# sensorboard_14.net
KiCad netlist of a schematic drawn in EAGLE
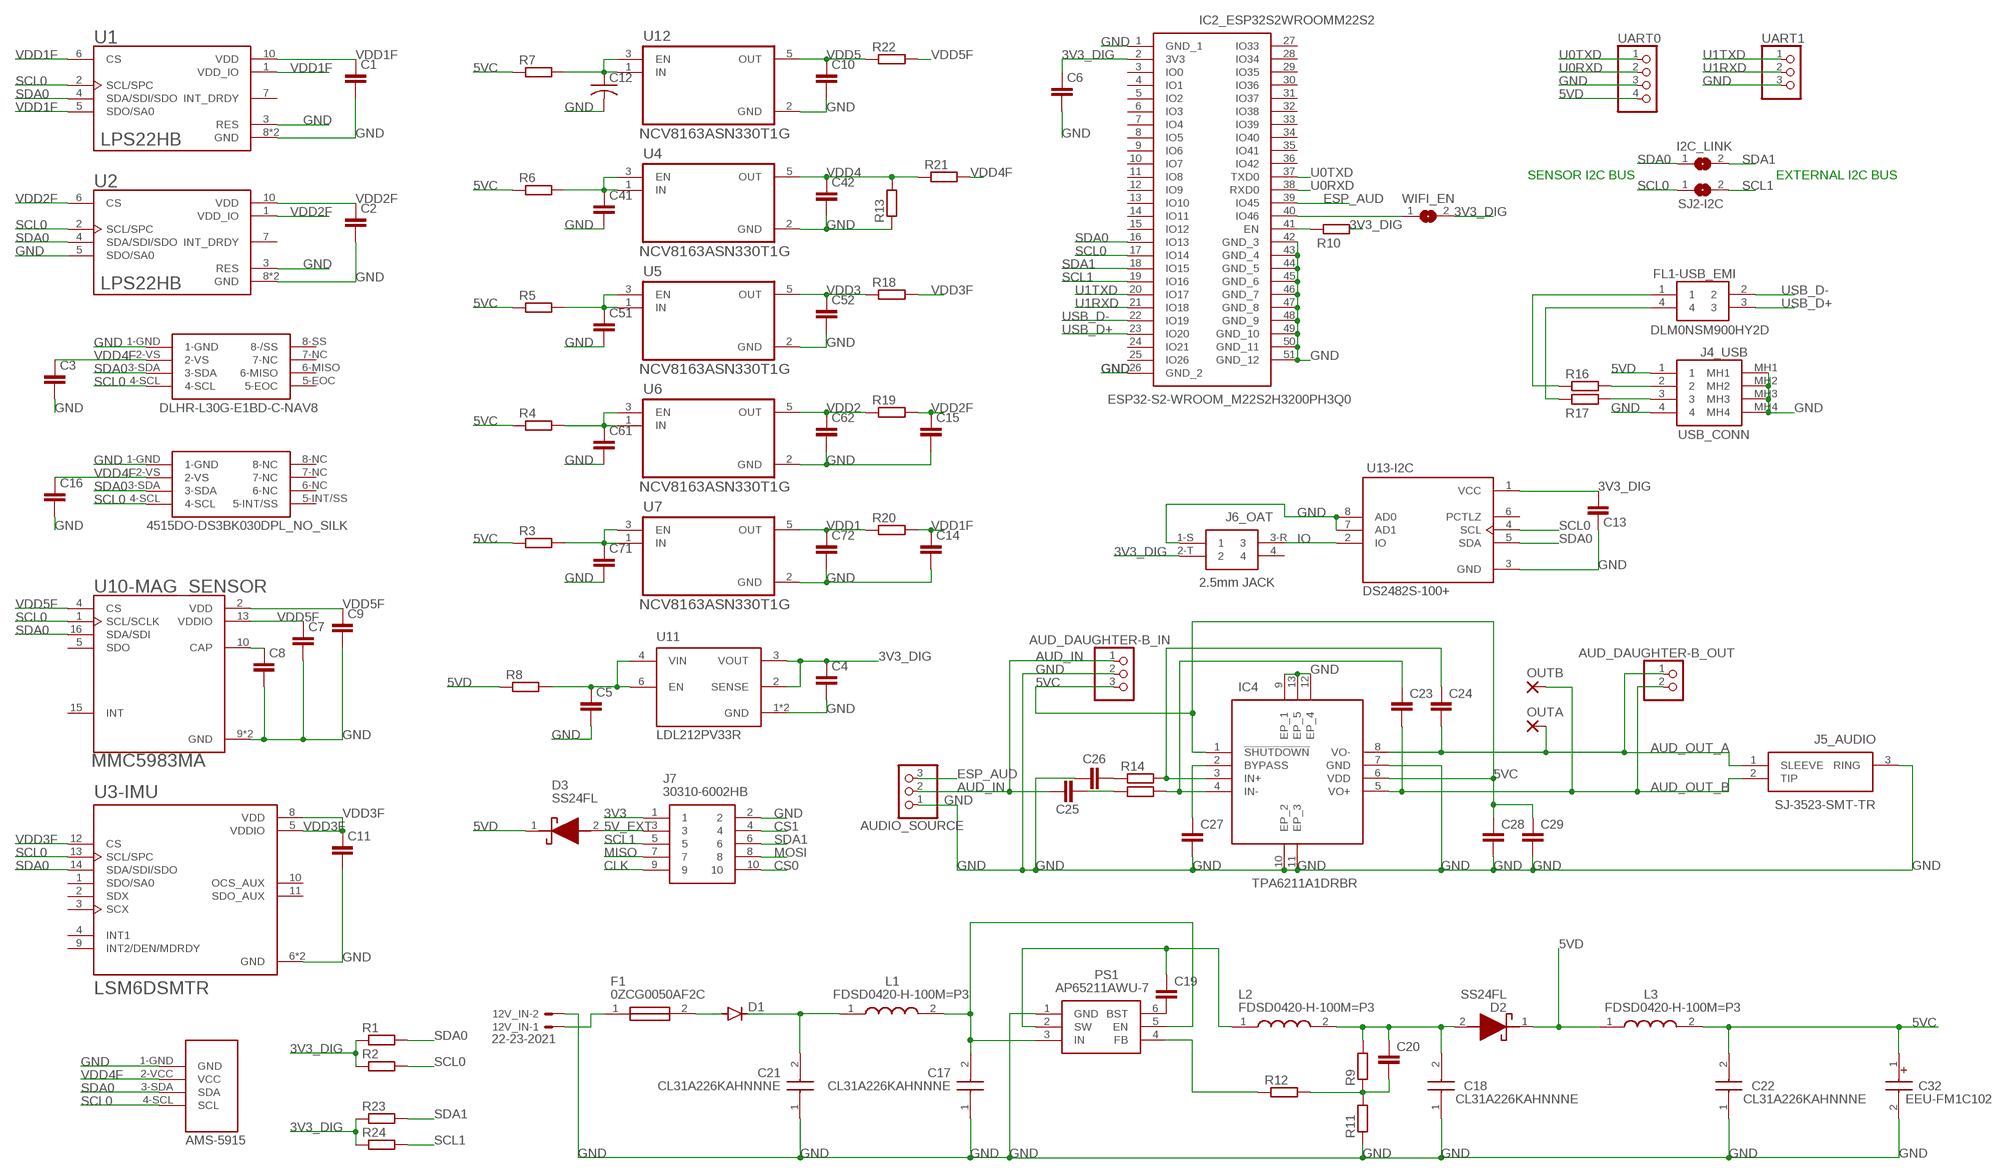
[diagram p0: schematic, sheet 1]

(export (version "E")
  (design (tool "Eeschema 10.0.6"))
  (components
    (comp (ref "12V_IN")
      (value "22-23-2021")
      (footprint "eagle-import:22-23-2021")
      (fields (field (name "MF") "MOLEX"))
      (libsource (lib "eagle-import") (part "22-23-2021"))
    )
    (comp (ref "AUDIO_SOURCE")
      (value "PINHD-1X3")
      (footprint "eagle-import:1X03")
      (libsource (lib "eagle-import") (part "PINHD-1X3"))
    )
    (comp (ref "AUD_DAUGHTER-B_IN")
      (value "PINHD-1X3")
      (footprint "eagle-import:1X03")
      (libsource (lib "eagle-import") (part "PINHD-1X3"))
    )
    (comp (ref "AUD_DAUGHTER-B_OUT")
      (value "PINHD-1X2")
      (footprint "eagle-import:1X02")
      (libsource (lib "eagle-import") (part "PINHD-1X2"))
    )
    (comp (ref "C1")
      (value "C-EUC0603")
      (footprint "eagle-import:C0603")
      (libsource (lib "eagle-import") (part "C-EUC0603"))
    )
    (comp (ref "C2")
      (value "C-EUC0603")
      (footprint "eagle-import:C0603")
      (libsource (lib "eagle-import") (part "C-EUC0603"))
    )
    (comp (ref "C3")
      (value "C-EUC0805")
      (footprint "eagle-import:C0805")
      (libsource (lib "eagle-import") (part "C-EUC0805"))
    )
    (comp (ref "C4")
      (value "C-EUC0805")
      (footprint "eagle-import:C0805")
      (libsource (lib "eagle-import") (part "C-EUC0805"))
    )
    (comp (ref "C5")
      (value "C-EUC0805")
      (footprint "eagle-import:C0805")
      (libsource (lib "eagle-import") (part "C-EUC0805"))
    )
    (comp (ref "C6")
      (value "C-EUC0805")
      (footprint "eagle-import:C0805")
      (libsource (lib "eagle-import") (part "C-EUC0805"))
    )
    (comp (ref "C7")
      (value "C-EUC0805")
      (footprint "eagle-import:C0805")
      (libsource (lib "eagle-import") (part "C-EUC0805"))
    )
    (comp (ref "C8")
      (value "C-EUC0805")
      (footprint "eagle-import:C0805")
      (libsource (lib "eagle-import") (part "C-EUC0805"))
    )
    (comp (ref "C9")
      (value "C-EUC0805")
      (footprint "eagle-import:C0805")
      (libsource (lib "eagle-import") (part "C-EUC0805"))
    )
    (comp (ref "C10")
      (value "C-EUC0805")
      (footprint "eagle-import:C0805")
      (libsource (lib "eagle-import") (part "C-EUC0805"))
    )
    (comp (ref "C11")
      (value "C-EUC0805")
      (footprint "eagle-import:C0805")
      (libsource (lib "eagle-import") (part "C-EUC0805"))
    )
    (comp (ref "C12")
      (value "C-USC0805")
      (footprint "eagle-import:C0805")
      (libsource (lib "eagle-import") (part "C-USC0805"))
    )
    (comp (ref "C13")
      (value "C-EUC0805")
      (footprint "eagle-import:C0805")
      (libsource (lib "eagle-import") (part "C-EUC0805"))
    )
    (comp (ref "C14")
      (value "C-EUC0805")
      (footprint "eagle-import:C0805")
      (libsource (lib "eagle-import") (part "C-EUC0805"))
    )
    (comp (ref "C15")
      (value "C-EUC0805")
      (footprint "eagle-import:C0805")
      (libsource (lib "eagle-import") (part "C-EUC0805"))
    )
    (comp (ref "C16")
      (value "C-EUC0805")
      (footprint "eagle-import:C0805")
      (libsource (lib "eagle-import") (part "C-EUC0805"))
    )
    (comp (ref "C17")
      (value "CL31A226KAHNNNE")
      (footprint "eagle-import:CAPC3216X180N")
      (libsource (lib "eagle-import") (part "CL31A226KAHNNNE"))
    )
    (comp (ref "C18")
      (value "CL31A226KAHNNNE")
      (footprint "eagle-import:CAPC3216X180N")
      (libsource (lib "eagle-import") (part "CL31A226KAHNNNE"))
    )
    (comp (ref "C19")
      (value "C-EUC0805")
      (footprint "eagle-import:C0805")
      (libsource (lib "eagle-import") (part "C-EUC0805"))
    )
    (comp (ref "C20")
      (value "C-EUC0805")
      (footprint "eagle-import:C0805")
      (libsource (lib "eagle-import") (part "C-EUC0805"))
    )
    (comp (ref "C21")
      (value "CL31A226KAHNNNE")
      (footprint "eagle-import:CAPC3216X180N")
      (libsource (lib "eagle-import") (part "CL31A226KAHNNNE"))
    )
    (comp (ref "C22")
      (value "CL31A226KAHNNNE")
      (footprint "eagle-import:CAPC3216X180N")
      (libsource (lib "eagle-import") (part "CL31A226KAHNNNE"))
    )
    (comp (ref "C23")
      (value "C-EUC0805")
      (footprint "eagle-import:C0805")
      (libsource (lib "eagle-import") (part "C-EUC0805"))
    )
    (comp (ref "C24")
      (value "C-EUC0805")
      (footprint "eagle-import:C0805")
      (libsource (lib "eagle-import") (part "C-EUC0805"))
    )
    (comp (ref "C25")
      (value "C-EUC1206")
      (footprint "eagle-import:C1206")
      (libsource (lib "eagle-import") (part "C-EUC1206"))
    )
    (comp (ref "C26")
      (value "C-EUC1206")
      (footprint "eagle-import:C1206")
      (libsource (lib "eagle-import") (part "C-EUC1206"))
    )
    (comp (ref "C27")
      (value "C-EUC1206")
      (footprint "eagle-import:C1206")
      (libsource (lib "eagle-import") (part "C-EUC1206"))
    )
    (comp (ref "C28")
      (value "C-EUC1206")
      (footprint "eagle-import:C1206")
      (libsource (lib "eagle-import") (part "C-EUC1206"))
    )
    (comp (ref "C29")
      (value "C-EUC1206")
      (footprint "eagle-import:C1206")
      (libsource (lib "eagle-import") (part "C-EUC1206"))
    )
    (comp (ref "C32")
      (value "EEU-FM1C102")
      (footprint "eagle-import:CAPPRD500W65D1000H2200")
      (fields (field (name "MOUSER_PART_NUMBER") "667-EEU-FM1C102"))
      (libsource (lib "eagle-import") (part "EEU-FM1C102"))
    )
    (comp (ref "C41")
      (value "C-EUC0805")
      (footprint "eagle-import:C0805")
      (libsource (lib "eagle-import") (part "C-EUC0805"))
    )
    (comp (ref "C42")
      (value "C-EUC0805")
      (footprint "eagle-import:C0805")
      (libsource (lib "eagle-import") (part "C-EUC0805"))
    )
    (comp (ref "C51")
      (value "C-EUC0805")
      (footprint "eagle-import:C0805")
      (libsource (lib "eagle-import") (part "C-EUC0805"))
    )
    (comp (ref "C52")
      (value "C-EUC0805")
      (footprint "eagle-import:C0805")
      (libsource (lib "eagle-import") (part "C-EUC0805"))
    )
    (comp (ref "C61")
      (value "C-EUC0805")
      (footprint "eagle-import:C0805")
      (libsource (lib "eagle-import") (part "C-EUC0805"))
    )
    (comp (ref "C62")
      (value "C-EUC0805")
      (footprint "eagle-import:C0805")
      (libsource (lib "eagle-import") (part "C-EUC0805"))
    )
    (comp (ref "C71")
      (value "C-EUC0805")
      (footprint "eagle-import:C0805")
      (libsource (lib "eagle-import") (part "C-EUC0805"))
    )
    (comp (ref "C72")
      (value "C-EUC0805")
      (footprint "eagle-import:C0805")
      (libsource (lib "eagle-import") (part "C-EUC0805"))
    )
    (comp (ref "D1")
      (value "DIODE-DO-214AC")
      (footprint "eagle-import:DO-214AC")
      (libsource (lib "eagle-import") (part "DIODE-DO-214AC"))
    )
    (comp (ref "D2")
      (value "SS24FL")
      (footprint "eagle-import:SODFL3617X108N")
      (fields (field (name "MOUSER_PART_NUMBER") "512-SS24FL"))
      (libsource (lib "eagle-import") (part "SS24FL"))
    )
    (comp (ref "D3")
      (value "SS24FL")
      (footprint "eagle-import:SODFL3617X108N")
      (fields (field (name "MOUSER_PART_NUMBER") "512-SS24FL"))
      (libsource (lib "eagle-import") (part "SS24FL"))
    )
    (comp (ref "DLHR-L30G-E1BD-C-NAV8")
      (value "DLHR-L30G-E1BD-C-NAV8")
      (footprint "eagle-import:DLHR-L30G-E1BD-C-NAV8")
      (libsource (lib "eagle-import") (part "DLHR-L30G-E1BD-C-NAV8"))
    )
    (comp (ref "F1")
      (value "0ZCG0050AF2C")
      (footprint "eagle-import:FUSC4632X75N")
      (fields (field (name "MOUSER_PART_NUMBER") "530-0ZCG0050AF2C"))
      (libsource (lib "eagle-import") (part "0ZCG0050AF2C"))
    )
    (comp (ref "FL1-USB_EMI")
      (value "DLM0NSM900HY2D")
      (footprint "eagle-import:DLM0NSB120HY2B")
      (fields (field (name "MOUSER_PART_NUMBER") "81-DLM0NSM900HY2D"))
      (libsource (lib "eagle-import") (part "DLM0NSM900HY2D"))
    )
    (comp (ref "I2C_LINK")
      (value "SJ")
      (footprint "eagle-import:SJ")
      (libsource (lib "eagle-import") (part "SJ"))
    )
    (comp (ref "IC2_ESP32S2WROOMM22S2")
      (value "ESP32-S2-WROOM_M22S2H3200PH3Q0")
      (footprint "eagle-import:ESP32S2WROOMM22S2H3200PH3Q0")
      (fields
        (field (name "MANUFACTURER_PART_NUMBER") "ESP32-S2-WROOM(M22S2H3200PH3Q0)")
        (field (name "MOUSER_PART_NUMBER") "356-ESP32S2WRM3200PH")
      )
      (libsource (lib "eagle-import") (part "ESP32-S2-WROOM_M22S2H3200PH3Q0"))
    )
    (comp (ref "IC4")
      (value "TPA6211A1DRBR")
      (footprint "eagle-import:TPS7A8033DRBT")
      (fields (field (name "MOUSER_PART_NUMBER") "595-TPA6211A1DRBR"))
      (libsource (lib "eagle-import") (part "TPA6211A1DRBR"))
    )
    (comp (ref "J4_USB")
      (value "USB_CONN")
      (footprint "eagle-import:737250110BLF")
      (fields
        (field (name "MANUFACTURER_PART_NUMBER") "73725-0110BLF")
        (field (name "MOUSER_PART_NUMBER") "649-73725-0110BLF")
      )
      (libsource (lib "eagle-import") (part "73725-0110BLF"))
    )
    (comp (ref "J5_AUDIO")
      (value "SJ-3523-SMT-TR")
      (footprint "eagle-import:SJ3523SMTTR")
      (fields (field (name "MOUSER_PART_NUMBER") "490-SJ-3523-SMT-TR"))
      (libsource (lib "eagle-import") (part "SJ-3523-SMT-TR"))
    )
    (comp (ref "J6_OAT")
      (value "2.5mm JACK")
      (footprint "eagle-import:SJ-2523-SMT-TR")
      (fields
        (field (name "MANUFACTURER_PART_NUMBER") "SJ-2523-SMT-TR")
        (field (name "MOUSER_PART_NUMBER") "490-SJ-2523-SMT-TR")
      )
      (libsource (lib "eagle-import") (part "SJ-2523-SMT-TR"))
    )
    (comp (ref "J7")
      (value "30310-6002HB")
      (footprint "eagle-import:SHDR10W64P254_2X5_2030X878X930")
      (fields (field (name "MOUSER_PART_NUMBER") "517-30310-6002"))
      (libsource (lib "eagle-import") (part "30310-6002HB"))
    )
    (comp (ref "L1")
      (value "FDSD0420-H-100M=P3")
      (footprint "eagle-import:FDSD0420WH150MP3")
      (fields (field (name "MOUSER_PART_NUMBER") "81-FDSD0420-H-100MP3"))
      (libsource (lib "eagle-import") (part "FDSD0420-H-100M=P3"))
    )
    (comp (ref "L2")
      (value "FDSD0420-H-100M=P3")
      (footprint "eagle-import:FDSD0420WH150MP3")
      (fields (field (name "MOUSER_PART_NUMBER") "81-FDSD0420-H-100MP3"))
      (libsource (lib "eagle-import") (part "FDSD0420-H-100M=P3"))
    )
    (comp (ref "L3")
      (value "FDSD0420-H-100M=P3")
      (footprint "eagle-import:FDSD0420WH150MP3")
      (fields (field (name "MOUSER_PART_NUMBER") "81-FDSD0420-H-100MP3"))
      (libsource (lib "eagle-import") (part "FDSD0420-H-100M=P3"))
    )
    (comp (ref "OUTA")
      (value "SMD2_SMALLSMALL")
      (footprint "eagle-import:SMD2_SMALL")
      (libsource (lib "eagle-import") (part "SMD2_SMALLSMALL"))
    )
    (comp (ref "OUTB")
      (value "SMD2_SMALLSMALL")
      (footprint "eagle-import:SMD2_SMALL")
      (libsource (lib "eagle-import") (part "SMD2_SMALLSMALL"))
    )
    (comp (ref "PS1")
      (value "AP65211AWU-7")
      (footprint "eagle-import:SOT95P280X90-6N")
      (fields (field (name "MOUSER_PART_NUMBER") "621-AP65211AWU-7"))
      (libsource (lib "eagle-import") (part "AP65211AWU-7"))
    )
    (comp (ref "R1")
      (value "R-EU_R0805")
      (footprint "eagle-import:R0805")
      (libsource (lib "eagle-import") (part "R-EU_R0805"))
    )
    (comp (ref "R2")
      (value "R-EU_R0805")
      (footprint "eagle-import:R0805")
      (libsource (lib "eagle-import") (part "R-EU_R0805"))
    )
    (comp (ref "R3")
      (value "R-EU_R0805")
      (footprint "eagle-import:R0805")
      (libsource (lib "eagle-import") (part "R-EU_R0805"))
    )
    (comp (ref "R4")
      (value "R-EU_R0805")
      (footprint "eagle-import:R0805")
      (libsource (lib "eagle-import") (part "R-EU_R0805"))
    )
    (comp (ref "R5")
      (value "R-EU_R0805")
      (footprint "eagle-import:R0805")
      (libsource (lib "eagle-import") (part "R-EU_R0805"))
    )
    (comp (ref "R6")
      (value "R-EU_R0805")
      (footprint "eagle-import:R0805")
      (libsource (lib "eagle-import") (part "R-EU_R0805"))
    )
    (comp (ref "R7")
      (value "R-EU_R0805")
      (footprint "eagle-import:R0805")
      (libsource (lib "eagle-import") (part "R-EU_R0805"))
    )
    (comp (ref "R8")
      (value "R-EU_R0805")
      (footprint "eagle-import:R0805")
      (libsource (lib "eagle-import") (part "R-EU_R0805"))
    )
    (comp (ref "R9")
      (value "R-EU_R0805")
      (footprint "eagle-import:R0805")
      (libsource (lib "eagle-import") (part "R-EU_R0805"))
    )
    (comp (ref "R10")
      (value "R-EU_R0805")
      (footprint "eagle-import:R0805")
      (libsource (lib "eagle-import") (part "R-EU_R0805"))
    )
    (comp (ref "R11")
      (value "R-EU_R0805")
      (footprint "eagle-import:R0805")
      (libsource (lib "eagle-import") (part "R-EU_R0805"))
    )
    (comp (ref "R12")
      (value "R-EU_R0805")
      (footprint "eagle-import:R0805")
      (libsource (lib "eagle-import") (part "R-EU_R0805"))
    )
    (comp (ref "R13")
      (value "R-EU_R0805")
      (footprint "eagle-import:R0805")
      (libsource (lib "eagle-import") (part "R-EU_R0805"))
    )
    (comp (ref "R14")
      (value "R-EU_R0805")
      (footprint "eagle-import:R0805")
      (libsource (lib "eagle-import") (part "R-EU_R0805"))
    )
    (comp (ref "R15")
      (value "R-EU_R0805")
      (footprint "eagle-import:R0805")
      (libsource (lib "eagle-import") (part "R-EU_R0805"))
    )
    (comp (ref "R16")
      (value "R-EU_R0805")
      (footprint "eagle-import:R0805")
      (libsource (lib "eagle-import") (part "R-EU_R0805"))
    )
    (comp (ref "R17")
      (value "R-EU_R0805")
      (footprint "eagle-import:R0805")
      (libsource (lib "eagle-import") (part "R-EU_R0805"))
    )
    (comp (ref "R18")
      (value "R-EU_R0805")
      (footprint "eagle-import:R0805")
      (libsource (lib "eagle-import") (part "R-EU_R0805"))
    )
    (comp (ref "R19")
      (value "R-EU_R0805")
      (footprint "eagle-import:R0805")
      (libsource (lib "eagle-import") (part "R-EU_R0805"))
    )
    (comp (ref "R20")
      (value "R-EU_R0805")
      (footprint "eagle-import:R0805")
      (libsource (lib "eagle-import") (part "R-EU_R0805"))
    )
    (comp (ref "R21")
      (value "R-EU_R0805")
      (footprint "eagle-import:R0805")
      (libsource (lib "eagle-import") (part "R-EU_R0805"))
    )
    (comp (ref "R22")
      (value "R-EU_R0805")
      (footprint "eagle-import:R0805")
      (libsource (lib "eagle-import") (part "R-EU_R0805"))
    )
    (comp (ref "R23")
      (value "R-EU_R0805")
      (footprint "eagle-import:R0805")
      (libsource (lib "eagle-import") (part "R-EU_R0805"))
    )
    (comp (ref "R24")
      (value "R-EU_R0805")
      (footprint "eagle-import:R0805")
      (libsource (lib "eagle-import") (part "R-EU_R0805"))
    )
    (comp (ref "SJ2-I2C")
      (value "SJ")
      (footprint "eagle-import:SJ")
      (libsource (lib "eagle-import") (part "SJ"))
    )
    (comp (ref "U$1")
      (value "AMS-5915")
      (footprint "eagle-import:AMS-5915")
      (libsource (lib "eagle-import") (part "AMS-5915"))
    )
    (comp (ref "U$4")
      (value "4515DO-DS3BK030DPL_NO_SILKNO_SILK")
      (footprint "eagle-import:4515DO-DS3BK030DPL_NO_SILK")
      (libsource (lib "eagle-import") (part "4515DO-DS3BK030DPL_NO_SILKNO_SILK"))
    )
    (comp (ref "U1")
      (value "LPS22HB")
      (footprint "eagle-import:LGA10R50P2X3_200X200X80")
      (fields (field (name "MF") "STMicroelectronics"))
      (libsource (lib "eagle-import") (part "LPS22HB"))
    )
    (comp (ref "U2")
      (value "LPS22HB")
      (footprint "eagle-import:LGA10R50P2X3_200X200X80")
      (fields (field (name "MF") "STMicroelectronics"))
      (libsource (lib "eagle-import") (part "LPS22HB"))
    )
    (comp (ref "U3-IMU")
      (value "LSM6DSMTR")
      (footprint "eagle-import:PQFN50P300X250X86-14N")
      (fields (field (name "MF") "STMicroelectronics"))
      (libsource (lib "eagle-import") (part "LSM6DSMTR"))
    )
    (comp (ref "U4")
      (value "NCV8163ASN330T1G")
      (footprint "eagle-import:SOP95P275X110-5N")
      (fields (field (name "MF") "ON Semiconductor"))
      (libsource (lib "eagle-import") (part "NCV8163ASN330T1G"))
    )
    (comp (ref "U5")
      (value "NCV8163ASN330T1G")
      (footprint "eagle-import:SOP95P275X110-5N")
      (fields (field (name "MF") "ON Semiconductor"))
      (libsource (lib "eagle-import") (part "NCV8163ASN330T1G"))
    )
    (comp (ref "U6")
      (value "NCV8163ASN330T1G")
      (footprint "eagle-import:SOP95P275X110-5N")
      (fields (field (name "MF") "ON Semiconductor"))
      (libsource (lib "eagle-import") (part "NCV8163ASN330T1G"))
    )
    (comp (ref "U7")
      (value "NCV8163ASN330T1G")
      (footprint "eagle-import:SOP95P275X110-5N")
      (fields (field (name "MF") "ON Semiconductor"))
      (libsource (lib "eagle-import") (part "NCV8163ASN330T1G"))
    )
    (comp (ref "U10-MAG_SENSOR")
      (value "MMC5983MA")
      (footprint "eagle-import:LGA16R50P4X4_330X330X100")
      (fields (field (name "MF") "ON Semiconductor") (field (name "MP") "FIS1100"))
      (libsource (lib "eagle-import") (part "MMC5983MA"))
    )
    (comp (ref "U11")
      (value "LDL212PV33R")
      (footprint "eagle-import:SON50P200X200X80-7N")
      (fields (field (name "MF") "STMicroelectronics"))
      (libsource (lib "eagle-import") (part "LDL212PV33R"))
    )
    (comp (ref "U12")
      (value "NCV8163ASN330T1G")
      (footprint "eagle-import:SOP95P275X110-5N")
      (fields (field (name "MF") "ON Semiconductor"))
      (libsource (lib "eagle-import") (part "NCV8163ASN330T1G"))
    )
    (comp (ref "U13-I2C")
      (value "DS2482S-100+")
      (footprint "eagle-import:SOIC127P600X175-8N")
      (fields (field (name "MF") "Maxim Integrated"))
      (libsource (lib "eagle-import") (part "DS2482S-100+"))
    )
    (comp (ref "UART0")
      (value "PINHD-1X4")
      (footprint "eagle-import:1X04")
      (libsource (lib "eagle-import") (part "PINHD-1X4"))
    )
    (comp (ref "UART1")
      (value "PINHD-1X3")
      (footprint "eagle-import:1X03")
      (libsource (lib "eagle-import") (part "PINHD-1X3"))
    )
    (comp (ref "WIFI_EN")
      (value "SJ")
      (footprint "eagle-import:SJ")
      (libsource (lib "eagle-import") (part "SJ"))
    )
  )
  (nets
    (net (code "1") (name "/3V3") (class "Default")
      (node (ref "J7") (pin "1") (pinfunction "1_1") (pintype "bidirectional"))
    )
    (net (code "2") (name "/3V3_DIG") (class "Default")
      (node (ref "C13") (pin "1") (pinfunction "1_1") (pintype "passive"))
      (node (ref "C4") (pin "1") (pinfunction "1_1") (pintype "passive"))
      (node (ref "C6") (pin "1") (pinfunction "1_1") (pintype "passive"))
      (node (ref "IC2_ESP32S2WROOMM22S2") (pin "2") (pinfunction "3V3_2") (pintype "bidirectional"))
      (node (ref "J6_OAT") (pin "2-T") (pinfunction "2_2-T") (pintype "bidirectional"))
      (node (ref "R1") (pin "1") (pinfunction "1_1") (pintype "passive"))
      (node (ref "R10") (pin "2") (pinfunction "2_2") (pintype "passive"))
      (node (ref "R2") (pin "1") (pinfunction "1_1") (pintype "passive"))
      (node (ref "R23") (pin "1") (pinfunction "1_1") (pintype "passive"))
      (node (ref "R24") (pin "1") (pinfunction "1_1") (pintype "passive"))
      (node (ref "U11") (pin "2") (pinfunction "SENSE_2") (pintype "input"))
      (node (ref "U11") (pin "3") (pinfunction "VOUT_3") (pintype "output"))
      (node (ref "U13-I2C") (pin "1") (pinfunction "VCC_1") (pintype "power_in"))
      (node (ref "WIFI_EN") (pin "2") (pinfunction "2_2") (pintype "passive"))
    )
    (net (code "3") (name "/5VC") (class "Default")
      (node (ref "AUD_DAUGHTER-B_IN") (pin "3") (pinfunction "3_3") (pintype "passive"))
      (node (ref "C22") (pin "2") (pinfunction "2_2") (pintype "bidirectional"))
      (node (ref "C28") (pin "1") (pinfunction "1_1") (pintype "passive"))
      (node (ref "C29") (pin "1") (pinfunction "1_1") (pintype "passive"))
      (node (ref "C32") (pin "1") (pinfunction "+_1") (pintype "bidirectional"))
      (node (ref "IC4") (pin "1") (pinfunction "~{SHUTDOWN}_1") (pintype "bidirectional"))
      (node (ref "IC4") (pin "6") (pinfunction "VDD_6") (pintype "bidirectional"))
      (node (ref "L3") (pin "2") (pinfunction "2_2") (pintype "bidirectional"))
      (node (ref "R3") (pin "1") (pinfunction "1_1") (pintype "passive"))
      (node (ref "R4") (pin "1") (pinfunction "1_1") (pintype "passive"))
      (node (ref "R5") (pin "1") (pinfunction "1_1") (pintype "passive"))
      (node (ref "R6") (pin "1") (pinfunction "1_1") (pintype "passive"))
      (node (ref "R7") (pin "1") (pinfunction "1_1") (pintype "passive"))
    )
    (net (code "4") (name "/5VD") (class "Default")
      (node (ref "D2") (pin "1") (pinfunction "K_1") (pintype "bidirectional"))
      (node (ref "D3") (pin "1") (pinfunction "K_1") (pintype "bidirectional"))
      (node (ref "J4_USB") (pin "1") (pinfunction "1_1") (pintype "bidirectional"))
      (node (ref "L3") (pin "1") (pinfunction "1_1") (pintype "bidirectional"))
      (node (ref "R8") (pin "1") (pinfunction "1_1") (pintype "passive"))
      (node (ref "UART0") (pin "4") (pinfunction "4_4") (pintype "passive"))
    )
    (net (code "5") (name "/5V_EXT") (class "Default")
      (node (ref "D3") (pin "2") (pinfunction "A_2") (pintype "bidirectional"))
      (node (ref "J7") (pin "3") (pinfunction "3_3") (pintype "bidirectional"))
    )
    (net (code "6") (name "/AUD_IN") (class "Default")
      (node (ref "AUDIO_SOURCE") (pin "2") (pinfunction "2_2") (pintype "passive"))
      (node (ref "AUD_DAUGHTER-B_IN") (pin "1") (pinfunction "1_1") (pintype "passive"))
      (node (ref "C25") (pin "1") (pinfunction "1_1") (pintype "passive"))
    )
    (net (code "7") (name "/AUD_OUT_A") (class "Default")
      (node (ref "AUD_DAUGHTER-B_OUT") (pin "1") (pinfunction "1_1") (pintype "passive"))
      (node (ref "C24") (pin "2") (pinfunction "2_2") (pintype "passive"))
      (node (ref "IC4") (pin "8") (pinfunction "VO-_8") (pintype "bidirectional"))
      (node (ref "J5_AUDIO") (pin "1") (pinfunction "SLEEVE_1") (pintype "bidirectional"))
      (node (ref "OUTA") (pin "1") (pinfunction "P_1") (pintype "passive"))
    )
    (net (code "8") (name "/AUD_OUT_B") (class "Default")
      (node (ref "AUD_DAUGHTER-B_OUT") (pin "2") (pinfunction "2_2") (pintype "passive"))
      (node (ref "C23") (pin "2") (pinfunction "2_2") (pintype "passive"))
      (node (ref "IC4") (pin "5") (pinfunction "VO+_5") (pintype "bidirectional"))
      (node (ref "J5_AUDIO") (pin "2") (pinfunction "TIP_2") (pintype "bidirectional"))
      (node (ref "OUTB") (pin "1") (pinfunction "P_1") (pintype "passive"))
    )
    (net (code "9") (name "/CLK") (class "Default")
      (node (ref "J7") (pin "9") (pinfunction "9_9") (pintype "bidirectional"))
    )
    (net (code "10") (name "/CS0") (class "Default")
      (node (ref "J7") (pin "10") (pinfunction "10_10") (pintype "bidirectional"))
    )
    (net (code "11") (name "/CS1") (class "Default")
      (node (ref "J7") (pin "4") (pinfunction "4_4") (pintype "bidirectional"))
    )
    (net (code "12") (name "/ESP_AUD") (class "Default")
      (node (ref "AUDIO_SOURCE") (pin "3") (pinfunction "3_3") (pintype "passive"))
      (node (ref "IC2_ESP32S2WROOMM22S2") (pin "39") (pinfunction "IO45_39") (pintype "bidirectional"))
    )
    (net (code "13") (name "/GND") (class "Default")
      (node (ref "12V_IN") (pin "2") (pinfunction "S_2") (pintype "passive"))
      (node (ref "AUDIO_SOURCE") (pin "1") (pinfunction "1_1") (pintype "passive"))
      (node (ref "AUD_DAUGHTER-B_IN") (pin "2") (pinfunction "2_2") (pintype "passive"))
      (node (ref "C1") (pin "2") (pinfunction "2_2") (pintype "passive"))
      (node (ref "C10") (pin "2") (pinfunction "2_2") (pintype "passive"))
      (node (ref "C11") (pin "2") (pinfunction "2_2") (pintype "passive"))
      (node (ref "C12") (pin "2") (pinfunction "2_2") (pintype "passive"))
      (node (ref "C13") (pin "2") (pinfunction "2_2") (pintype "passive"))
      (node (ref "C14") (pin "2") (pinfunction "2_2") (pintype "passive"))
      (node (ref "C15") (pin "2") (pinfunction "2_2") (pintype "passive"))
      (node (ref "C16") (pin "2") (pinfunction "2_2") (pintype "passive"))
      (node (ref "C17") (pin "1") (pinfunction "1_1") (pintype "bidirectional"))
      (node (ref "C18") (pin "1") (pinfunction "1_1") (pintype "bidirectional"))
      (node (ref "C2") (pin "2") (pinfunction "2_2") (pintype "passive"))
      (node (ref "C21") (pin "1") (pinfunction "1_1") (pintype "bidirectional"))
      (node (ref "C22") (pin "1") (pinfunction "1_1") (pintype "bidirectional"))
      (node (ref "C26") (pin "1") (pinfunction "1_1") (pintype "passive"))
      (node (ref "C27") (pin "2") (pinfunction "2_2") (pintype "passive"))
      (node (ref "C28") (pin "2") (pinfunction "2_2") (pintype "passive"))
      (node (ref "C29") (pin "2") (pinfunction "2_2") (pintype "passive"))
      (node (ref "C3") (pin "2") (pinfunction "2_2") (pintype "passive"))
      (node (ref "C32") (pin "2") (pinfunction "-_2") (pintype "bidirectional"))
      (node (ref "C4") (pin "2") (pinfunction "2_2") (pintype "passive"))
      (node (ref "C41") (pin "2") (pinfunction "2_2") (pintype "passive"))
      (node (ref "C42") (pin "2") (pinfunction "2_2") (pintype "passive"))
      (node (ref "C5") (pin "2") (pinfunction "2_2") (pintype "passive"))
      (node (ref "C51") (pin "2") (pinfunction "2_2") (pintype "passive"))
      (node (ref "C52") (pin "2") (pinfunction "2_2") (pintype "passive"))
      (node (ref "C6") (pin "2") (pinfunction "2_2") (pintype "passive"))
      (node (ref "C61") (pin "2") (pinfunction "2_2") (pintype "passive"))
      (node (ref "C62") (pin "2") (pinfunction "2_2") (pintype "passive"))
      (node (ref "C7") (pin "2") (pinfunction "2_2") (pintype "passive"))
      (node (ref "C71") (pin "2") (pinfunction "2_2") (pintype "passive"))
      (node (ref "C72") (pin "2") (pinfunction "2_2") (pintype "passive"))
      (node (ref "C8") (pin "2") (pinfunction "2_2") (pintype "passive"))
      (node (ref "C9") (pin "2") (pinfunction "2_2") (pintype "passive"))
      (node (ref "DLHR-L30G-E1BD-C-NAV8") (pin "1-GND") (pinfunction "1-GND_1-GND") (pintype "power_in"))
      (node (ref "IC2_ESP32S2WROOMM22S2") (pin "1") (pinfunction "GND_1_1") (pintype "bidirectional"))
      (node (ref "IC2_ESP32S2WROOMM22S2") (pin "26") (pinfunction "GND_2_26") (pintype "bidirectional"))
      (node (ref "IC2_ESP32S2WROOMM22S2") (pin "42") (pinfunction "GND_3_42") (pintype "bidirectional"))
      (node (ref "IC2_ESP32S2WROOMM22S2") (pin "43") (pinfunction "GND_4_43") (pintype "bidirectional"))
      (node (ref "IC2_ESP32S2WROOMM22S2") (pin "44") (pinfunction "GND_5_44") (pintype "bidirectional"))
      (node (ref "IC2_ESP32S2WROOMM22S2") (pin "45") (pinfunction "GND_6_45") (pintype "bidirectional"))
      (node (ref "IC2_ESP32S2WROOMM22S2") (pin "46") (pinfunction "GND_7_46") (pintype "bidirectional"))
      (node (ref "IC2_ESP32S2WROOMM22S2") (pin "47") (pinfunction "GND_8_47") (pintype "bidirectional"))
      (node (ref "IC2_ESP32S2WROOMM22S2") (pin "48") (pinfunction "GND_9_48") (pintype "bidirectional"))
      (node (ref "IC2_ESP32S2WROOMM22S2") (pin "49") (pinfunction "GND_10_49") (pintype "bidirectional"))
      (node (ref "IC2_ESP32S2WROOMM22S2") (pin "50") (pinfunction "GND_11_50") (pintype "bidirectional"))
      (node (ref "IC2_ESP32S2WROOMM22S2") (pin "51") (pinfunction "GND_12_51") (pintype "bidirectional"))
      (node (ref "IC4") (pin "10") (pinfunction "EP_2_10") (pintype "bidirectional"))
      (node (ref "IC4") (pin "11") (pinfunction "EP_3_11") (pintype "bidirectional"))
      (node (ref "IC4") (pin "12") (pinfunction "EP_4_12") (pintype "bidirectional"))
      (node (ref "IC4") (pin "13") (pinfunction "EP_5_13") (pintype "bidirectional"))
      (node (ref "IC4") (pin "7") (pinfunction "GND_7") (pintype "bidirectional"))
      (node (ref "IC4") (pin "9") (pinfunction "EP_1_9") (pintype "bidirectional"))
      (node (ref "J4_USB") (pin "4") (pinfunction "4_4") (pintype "bidirectional"))
      (node (ref "J4_USB") (pin "MH1") (pinfunction "MH1_MH1") (pintype "bidirectional"))
      (node (ref "J4_USB") (pin "MH2") (pinfunction "MH2_MH2") (pintype "bidirectional"))
      (node (ref "J4_USB") (pin "MH3") (pinfunction "MH3_MH3") (pintype "bidirectional"))
      (node (ref "J4_USB") (pin "MH4") (pinfunction "MH4_MH4") (pintype "bidirectional"))
      (node (ref "J5_AUDIO") (pin "3") (pinfunction "RING_3") (pintype "bidirectional"))
      (node (ref "J6_OAT") (pin "1-S") (pinfunction "1_1-S") (pintype "bidirectional"))
      (node (ref "J7") (pin "2") (pinfunction "2_2") (pintype "bidirectional"))
      (node (ref "PS1") (pin "1") (pinfunction "GND_1") (pintype "power_in"))
      (node (ref "R11") (pin "1") (pinfunction "1_1") (pintype "passive"))
      (node (ref "R13") (pin "1") (pinfunction "1_1") (pintype "passive"))
      (node (ref "U$1") (pin "1-GND") (pinfunction "GND_1-GND") (pintype "bidirectional"))
      (node (ref "U$4") (pin "1-GND") (pinfunction "1-GND_1-GND") (pintype "power_in"))
      (node (ref "U1") (pin "3") (pinfunction "RES_3") (pintype "power_in"))
      (node (ref "U1") (pin "8") (pinfunction "GND_8") (pintype "power_in"))
      (node (ref "U1") (pin "9") (pinfunction "GND_9") (pintype "power_in"))
      (node (ref "U10-MAG_SENSOR") (pin "11") (pinfunction "GND_11") (pintype "power_in"))
      (node (ref "U10-MAG_SENSOR") (pin "9") (pinfunction "GND_9") (pintype "power_in"))
      (node (ref "U11") (pin "1") (pinfunction "GND_1") (pintype "power_in"))
      (node (ref "U11") (pin "7") (pinfunction "GND_7") (pintype "power_in"))
      (node (ref "U12") (pin "2") (pinfunction "GND_2") (pintype "power_in"))
      (node (ref "U13-I2C") (pin "3") (pinfunction "GND_3") (pintype "power_in"))
      (node (ref "U13-I2C") (pin "7") (pinfunction "AD1_7") (pintype "input"))
      (node (ref "U13-I2C") (pin "8") (pinfunction "AD0_8") (pintype "input"))
      (node (ref "U2") (pin "3") (pinfunction "RES_3") (pintype "power_in"))
      (node (ref "U2") (pin "5") (pinfunction "SDO/SA0_5") (pintype "bidirectional"))
      (node (ref "U2") (pin "8") (pinfunction "GND_8") (pintype "power_in"))
      (node (ref "U2") (pin "9") (pinfunction "GND_9") (pintype "power_in"))
      (node (ref "U3-IMU") (pin "6") (pinfunction "GND_6") (pintype "power_in"))
      (node (ref "U3-IMU") (pin "7") (pinfunction "GND_7") (pintype "power_in"))
      (node (ref "U4") (pin "2") (pinfunction "GND_2") (pintype "power_in"))
      (node (ref "U5") (pin "2") (pinfunction "GND_2") (pintype "power_in"))
      (node (ref "U6") (pin "2") (pinfunction "GND_2") (pintype "power_in"))
      (node (ref "U7") (pin "2") (pinfunction "GND_2") (pintype "power_in"))
      (node (ref "UART0") (pin "3") (pinfunction "3_3") (pintype "passive"))
      (node (ref "UART1") (pin "3") (pinfunction "3_3") (pintype "passive"))
    )
    (net (code "14") (name "/IO") (class "Default")
      (node (ref "J6_OAT") (pin "3-R") (pinfunction "3_3-R") (pintype "bidirectional"))
      (node (ref "U13-I2C") (pin "2") (pinfunction "IO_2") (pintype "bidirectional"))
    )
    (net (code "15") (name "/MISO") (class "Default")
      (node (ref "J7") (pin "7") (pinfunction "7_7") (pintype "bidirectional"))
    )
    (net (code "16") (name "/MOSI") (class "Default")
      (node (ref "J7") (pin "8") (pinfunction "8_8") (pintype "bidirectional"))
    )
    (net (code "17") (name "/SCL0") (class "Default")
      (node (ref "DLHR-L30G-E1BD-C-NAV8") (pin "4-SCL") (pinfunction "4-SCL_4-SCL") (pintype "bidirectional"))
      (node (ref "IC2_ESP32S2WROOMM22S2") (pin "17") (pinfunction "IO14_17") (pintype "bidirectional"))
      (node (ref "R2") (pin "2") (pinfunction "2_2") (pintype "passive"))
      (node (ref "SJ2-I2C") (pin "1") (pinfunction "1_1") (pintype "passive"))
      (node (ref "U$1") (pin "4-SCL") (pinfunction "SCL_4-SCL") (pintype "bidirectional"))
      (node (ref "U$4") (pin "4-SCL") (pinfunction "4-SCL_4-SCL") (pintype "bidirectional"))
      (node (ref "U1") (pin "2") (pinfunction "SCL/SPC_2") (pintype "input"))
      (node (ref "U10-MAG_SENSOR") (pin "1") (pinfunction "SCL/SCLK_1") (pintype "bidirectional"))
      (node (ref "U13-I2C") (pin "4") (pinfunction "SCL_4") (pintype "input"))
      (node (ref "U2") (pin "2") (pinfunction "SCL/SPC_2") (pintype "input"))
      (node (ref "U3-IMU") (pin "13") (pinfunction "SCL/SPC_13") (pintype "input"))
    )
    (net (code "18") (name "/SCL1") (class "Default")
      (node (ref "IC2_ESP32S2WROOMM22S2") (pin "19") (pinfunction "IO16_19") (pintype "bidirectional"))
      (node (ref "J7") (pin "5") (pinfunction "5_5") (pintype "bidirectional"))
      (node (ref "R24") (pin "2") (pinfunction "2_2") (pintype "passive"))
      (node (ref "SJ2-I2C") (pin "2") (pinfunction "2_2") (pintype "passive"))
    )
    (net (code "19") (name "/SDA0") (class "Default")
      (node (ref "DLHR-L30G-E1BD-C-NAV8") (pin "3-SDA") (pinfunction "3-SDA_3-SDA") (pintype "bidirectional"))
      (node (ref "I2C_LINK") (pin "1") (pinfunction "1_1") (pintype "passive"))
      (node (ref "IC2_ESP32S2WROOMM22S2") (pin "16") (pinfunction "IO13_16") (pintype "bidirectional"))
      (node (ref "R1") (pin "2") (pinfunction "2_2") (pintype "passive"))
      (node (ref "U$1") (pin "3-SDA") (pinfunction "SDA_3-SDA") (pintype "bidirectional"))
      (node (ref "U$4") (pin "3-SDA") (pinfunction "3-SDA_3-SDA") (pintype "bidirectional"))
      (node (ref "U1") (pin "4") (pinfunction "SDA/SDI/SDO_4") (pintype "bidirectional"))
      (node (ref "U10-MAG_SENSOR") (pin "16") (pinfunction "SDA/SDI_16") (pintype "bidirectional"))
      (node (ref "U13-I2C") (pin "5") (pinfunction "SDA_5") (pintype "bidirectional"))
      (node (ref "U2") (pin "4") (pinfunction "SDA/SDI/SDO_4") (pintype "bidirectional"))
      (node (ref "U3-IMU") (pin "14") (pinfunction "SDA/SDI/SDO_14") (pintype "bidirectional"))
    )
    (net (code "20") (name "/SDA1") (class "Default")
      (node (ref "I2C_LINK") (pin "2") (pinfunction "2_2") (pintype "passive"))
      (node (ref "IC2_ESP32S2WROOMM22S2") (pin "18") (pinfunction "IO15_18") (pintype "bidirectional"))
      (node (ref "J7") (pin "6") (pinfunction "6_6") (pintype "bidirectional"))
      (node (ref "R23") (pin "2") (pinfunction "2_2") (pintype "passive"))
    )
    (net (code "21") (name "/U0RXD") (class "Default")
      (node (ref "IC2_ESP32S2WROOMM22S2") (pin "38") (pinfunction "RXD0_38") (pintype "bidirectional"))
      (node (ref "UART0") (pin "2") (pinfunction "2_2") (pintype "passive"))
    )
    (net (code "22") (name "/U0TXD") (class "Default")
      (node (ref "IC2_ESP32S2WROOMM22S2") (pin "37") (pinfunction "TXD0_37") (pintype "bidirectional"))
      (node (ref "UART0") (pin "1") (pinfunction "1_1") (pintype "passive"))
    )
    (net (code "23") (name "/U1RXD") (class "Default")
      (node (ref "IC2_ESP32S2WROOMM22S2") (pin "21") (pinfunction "IO18_21") (pintype "bidirectional"))
      (node (ref "UART1") (pin "2") (pinfunction "2_2") (pintype "passive"))
    )
    (net (code "24") (name "/U1TXD") (class "Default")
      (node (ref "IC2_ESP32S2WROOMM22S2") (pin "20") (pinfunction "IO17_20") (pintype "bidirectional"))
      (node (ref "UART1") (pin "1") (pinfunction "1_1") (pintype "passive"))
    )
    (net (code "25") (name "/USB_D+") (class "Default")
      (node (ref "FL1-USB_EMI") (pin "3") (pinfunction "3_3") (pintype "bidirectional"))
      (node (ref "IC2_ESP32S2WROOMM22S2") (pin "23") (pinfunction "IO20_23") (pintype "bidirectional"))
    )
    (net (code "26") (name "/USB_D-") (class "Default")
      (node (ref "FL1-USB_EMI") (pin "2") (pinfunction "2_2") (pintype "bidirectional"))
      (node (ref "IC2_ESP32S2WROOMM22S2") (pin "22") (pinfunction "IO19_22") (pintype "bidirectional"))
    )
    (net (code "27") (name "/VDD1") (class "Default")
      (node (ref "C72") (pin "1") (pinfunction "1_1") (pintype "passive"))
      (node (ref "R20") (pin "1") (pinfunction "1_1") (pintype "passive"))
      (node (ref "U7") (pin "5") (pinfunction "OUT_5") (pintype "output"))
    )
    (net (code "28") (name "/VDD1F") (class "Default")
      (node (ref "C1") (pin "1") (pinfunction "1_1") (pintype "passive"))
      (node (ref "C14") (pin "1") (pinfunction "1_1") (pintype "passive"))
      (node (ref "R20") (pin "2") (pinfunction "2_2") (pintype "passive"))
      (node (ref "U1") (pin "1") (pinfunction "VDD_IO_1") (pintype "power_in"))
      (node (ref "U1") (pin "10") (pinfunction "VDD_10") (pintype "power_in"))
      (node (ref "U1") (pin "5") (pinfunction "SDO/SA0_5") (pintype "bidirectional"))
      (node (ref "U1") (pin "6") (pinfunction "CS_6") (pintype "input"))
    )
    (net (code "29") (name "/VDD2") (class "Default")
      (node (ref "C62") (pin "1") (pinfunction "1_1") (pintype "passive"))
      (node (ref "R19") (pin "1") (pinfunction "1_1") (pintype "passive"))
      (node (ref "U6") (pin "5") (pinfunction "OUT_5") (pintype "output"))
    )
    (net (code "30") (name "/VDD2F") (class "Default")
      (node (ref "C15") (pin "1") (pinfunction "1_1") (pintype "passive"))
      (node (ref "C2") (pin "1") (pinfunction "1_1") (pintype "passive"))
      (node (ref "R19") (pin "2") (pinfunction "2_2") (pintype "passive"))
      (node (ref "U2") (pin "1") (pinfunction "VDD_IO_1") (pintype "power_in"))
      (node (ref "U2") (pin "10") (pinfunction "VDD_10") (pintype "power_in"))
      (node (ref "U2") (pin "6") (pinfunction "CS_6") (pintype "input"))
    )
    (net (code "31") (name "/VDD3") (class "Default")
      (node (ref "C52") (pin "1") (pinfunction "1_1") (pintype "passive"))
      (node (ref "R18") (pin "1") (pinfunction "1_1") (pintype "passive"))
      (node (ref "U5") (pin "5") (pinfunction "OUT_5") (pintype "output"))
    )
    (net (code "32") (name "/VDD3F") (class "Default")
      (node (ref "C11") (pin "1") (pinfunction "1_1") (pintype "passive"))
      (node (ref "R18") (pin "2") (pinfunction "2_2") (pintype "passive"))
      (node (ref "U3-IMU") (pin "12") (pinfunction "CS_12") (pintype "input"))
      (node (ref "U3-IMU") (pin "5") (pinfunction "VDDIO_5") (pintype "power_in"))
      (node (ref "U3-IMU") (pin "8") (pinfunction "VDD_8") (pintype "power_in"))
    )
    (net (code "33") (name "/VDD4") (class "Default")
      (node (ref "C42") (pin "1") (pinfunction "1_1") (pintype "passive"))
      (node (ref "R13") (pin "2") (pinfunction "2_2") (pintype "passive"))
      (node (ref "R21") (pin "1") (pinfunction "1_1") (pintype "passive"))
      (node (ref "U4") (pin "5") (pinfunction "OUT_5") (pintype "output"))
    )
    (net (code "34") (name "/VDD4F") (class "Default")
      (node (ref "C16") (pin "1") (pinfunction "1_1") (pintype "passive"))
      (node (ref "C3") (pin "1") (pinfunction "1_1") (pintype "passive"))
      (node (ref "DLHR-L30G-E1BD-C-NAV8") (pin "2-VS") (pinfunction "2-VS_2-VS") (pintype "power_in"))
      (node (ref "R21") (pin "2") (pinfunction "2_2") (pintype "passive"))
      (node (ref "U$1") (pin "2-VCC") (pinfunction "VCC_2-VCC") (pintype "bidirectional"))
      (node (ref "U$4") (pin "2-VS") (pinfunction "2-VS_2-VS") (pintype "power_in"))
    )
    (net (code "35") (name "/VDD5") (class "Default")
      (node (ref "C10") (pin "1") (pinfunction "1_1") (pintype "passive"))
      (node (ref "R22") (pin "1") (pinfunction "1_1") (pintype "passive"))
      (node (ref "U12") (pin "5") (pinfunction "OUT_5") (pintype "output"))
    )
    (net (code "36") (name "/VDD5F") (class "Default")
      (node (ref "C7") (pin "1") (pinfunction "1_1") (pintype "passive"))
      (node (ref "C9") (pin "1") (pinfunction "1_1") (pintype "passive"))
      (node (ref "R22") (pin "2") (pinfunction "2_2") (pintype "passive"))
      (node (ref "U10-MAG_SENSOR") (pin "13") (pinfunction "VDDIO_13") (pintype "power_in"))
      (node (ref "U10-MAG_SENSOR") (pin "2") (pinfunction "VDD_2") (pintype "power_in"))
      (node (ref "U10-MAG_SENSOR") (pin "4") (pinfunction "CS_4") (pintype "input"))
    )
    (net (code "37") (name "Net-(12V_INA-S)") (class "Default")
      (node (ref "12V_IN") (pin "1") (pinfunction "S_1") (pintype "passive"))
      (node (ref "F1") (pin "1") (pinfunction "1_1") (pintype "bidirectional"))
    )
    (net (code "38") (name "Net-(C20-Pad2)") (class "Default")
      (node (ref "C20") (pin "2") (pinfunction "2_2") (pintype "passive"))
      (node (ref "R11") (pin "2") (pinfunction "2_2") (pintype "passive"))
      (node (ref "R12") (pin "2") (pinfunction "2_2") (pintype "passive"))
      (node (ref "R9") (pin "1") (pinfunction "1_1") (pintype "passive"))
    )
    (net (code "39") (name "Net-(C21-Pad2)") (class "Default")
      (node (ref "C21") (pin "2") (pinfunction "2_2") (pintype "bidirectional"))
      (node (ref "D1") (pin "C") (pinfunction "C_C") (pintype "passive"))
      (node (ref "L1") (pin "1") (pinfunction "1_1") (pintype "bidirectional"))
    )
    (net (code "40") (name "Net-(C25-Pad2)") (class "Default")
      (node (ref "C25") (pin "2") (pinfunction "2_2") (pintype "passive"))
      (node (ref "R15") (pin "1") (pinfunction "1_1") (pintype "passive"))
    )
    (net (code "41") (name "Net-(C26-Pad2)") (class "Default")
      (node (ref "C26") (pin "2") (pinfunction "2_2") (pintype "passive"))
      (node (ref "R14") (pin "1") (pinfunction "1_1") (pintype "passive"))
    )
    (net (code "42") (name "Net-(D1-PadA)") (class "Default")
      (node (ref "D1") (pin "A") (pinfunction "A_A") (pintype "passive"))
      (node (ref "F1") (pin "2") (pinfunction "2_2") (pintype "bidirectional"))
    )
    (net (code "43") (name "Net-(D2-A)") (class "Default")
      (node (ref "C18") (pin "2") (pinfunction "2_2") (pintype "bidirectional"))
      (node (ref "C20") (pin "1") (pinfunction "1_1") (pintype "passive"))
      (node (ref "D2") (pin "2") (pinfunction "A_2") (pintype "bidirectional"))
      (node (ref "L2") (pin "2") (pinfunction "2_2") (pintype "bidirectional"))
      (node (ref "R9") (pin "2") (pinfunction "2_2") (pintype "passive"))
    )
    (net (code "44") (name "Net-(FL1-USB_EMI-Pad1)") (class "Default")
      (node (ref "FL1-USB_EMI") (pin "1") (pinfunction "1_1") (pintype "bidirectional"))
      (node (ref "R16") (pin "1") (pinfunction "1_1") (pintype "passive"))
    )
    (net (code "45") (name "Net-(FL1-USB_EMI-Pad4)") (class "Default")
      (node (ref "FL1-USB_EMI") (pin "4") (pinfunction "4_4") (pintype "bidirectional"))
      (node (ref "R17") (pin "1") (pinfunction "1_1") (pintype "passive"))
    )
    (net (code "46") (name "Net-(IC2_ESP32S2WROOMM22S2-EN)") (class "Default")
      (node (ref "IC2_ESP32S2WROOMM22S2") (pin "41") (pinfunction "EN_41") (pintype "bidirectional"))
      (node (ref "R10") (pin "1") (pinfunction "1_1") (pintype "passive"))
    )
    (net (code "47") (name "Net-(IC2_ESP32S2WROOMM22S2-IO46)") (class "Default")
      (node (ref "IC2_ESP32S2WROOMM22S2") (pin "40") (pinfunction "IO46_40") (pintype "bidirectional"))
      (node (ref "WIFI_EN") (pin "1") (pinfunction "1_1") (pintype "passive"))
    )
    (net (code "48") (name "Net-(IC4-BYPASS)") (class "Default")
      (node (ref "C27") (pin "1") (pinfunction "1_1") (pintype "passive"))
      (node (ref "IC4") (pin "2") (pinfunction "BYPASS_2") (pintype "bidirectional"))
    )
    (net (code "49") (name "Net-(IC4-IN+)") (class "Default")
      (node (ref "C24") (pin "1") (pinfunction "1_1") (pintype "passive"))
      (node (ref "IC4") (pin "3") (pinfunction "IN+_3") (pintype "bidirectional"))
      (node (ref "R14") (pin "2") (pinfunction "2_2") (pintype "passive"))
    )
    (net (code "50") (name "Net-(IC4-IN-)") (class "Default")
      (node (ref "C23") (pin "1") (pinfunction "1_1") (pintype "passive"))
      (node (ref "IC4") (pin "4") (pinfunction "IN-_4") (pintype "bidirectional"))
      (node (ref "R15") (pin "2") (pinfunction "2_2") (pintype "passive"))
    )
    (net (code "51") (name "Net-(J4_USB-Pad2)") (class "Default")
      (node (ref "J4_USB") (pin "2") (pinfunction "2_2") (pintype "bidirectional"))
      (node (ref "R16") (pin "2") (pinfunction "2_2") (pintype "passive"))
    )
    (net (code "52") (name "Net-(J4_USB-Pad3)") (class "Default")
      (node (ref "J4_USB") (pin "3") (pinfunction "3_3") (pintype "bidirectional"))
      (node (ref "R17") (pin "2") (pinfunction "2_2") (pintype "passive"))
    )
    (net (code "53") (name "Net-(PS1-BST)") (class "Default")
      (node (ref "C19") (pin "2") (pinfunction "2_2") (pintype "passive"))
      (node (ref "PS1") (pin "6") (pinfunction "BST_6") (pintype "input"))
    )
    (net (code "54") (name "Net-(PS1-EN)") (class "Default")
      (node (ref "C17") (pin "2") (pinfunction "2_2") (pintype "bidirectional"))
      (node (ref "L1") (pin "2") (pinfunction "2_2") (pintype "bidirectional"))
      (node (ref "PS1") (pin "3") (pinfunction "IN_3") (pintype "input"))
      (node (ref "PS1") (pin "5") (pinfunction "EN_5") (pintype "input"))
    )
    (net (code "55") (name "Net-(PS1-FB)") (class "Default")
      (node (ref "PS1") (pin "4") (pinfunction "FB_4") (pintype "input"))
      (node (ref "R12") (pin "1") (pinfunction "1_1") (pintype "passive"))
    )
    (net (code "56") (name "Net-(PS1-SW)") (class "Default")
      (node (ref "C19") (pin "1") (pinfunction "1_1") (pintype "passive"))
      (node (ref "L2") (pin "1") (pinfunction "1_1") (pintype "bidirectional"))
      (node (ref "PS1") (pin "2") (pinfunction "SW_2") (pintype "output"))
    )
    (net (code "57") (name "Net-(U4-EN)") (class "Default")
      (node (ref "C41") (pin "1") (pinfunction "1_1") (pintype "passive"))
      (node (ref "R6") (pin "2") (pinfunction "2_2") (pintype "passive"))
      (node (ref "U4") (pin "1") (pinfunction "IN_1") (pintype "input"))
      (node (ref "U4") (pin "3") (pinfunction "EN_3") (pintype "input"))
    )
    (net (code "58") (name "Net-(U5-EN)") (class "Default")
      (node (ref "C51") (pin "1") (pinfunction "1_1") (pintype "passive"))
      (node (ref "R5") (pin "2") (pinfunction "2_2") (pintype "passive"))
      (node (ref "U5") (pin "1") (pinfunction "IN_1") (pintype "input"))
      (node (ref "U5") (pin "3") (pinfunction "EN_3") (pintype "input"))
    )
    (net (code "59") (name "Net-(U6-EN)") (class "Default")
      (node (ref "C61") (pin "1") (pinfunction "1_1") (pintype "passive"))
      (node (ref "R4") (pin "2") (pinfunction "2_2") (pintype "passive"))
      (node (ref "U6") (pin "1") (pinfunction "IN_1") (pintype "input"))
      (node (ref "U6") (pin "3") (pinfunction "EN_3") (pintype "input"))
    )
    (net (code "60") (name "Net-(U7-EN)") (class "Default")
      (node (ref "C71") (pin "1") (pinfunction "1_1") (pintype "passive"))
      (node (ref "R3") (pin "2") (pinfunction "2_2") (pintype "passive"))
      (node (ref "U7") (pin "1") (pinfunction "IN_1") (pintype "input"))
      (node (ref "U7") (pin "3") (pinfunction "EN_3") (pintype "input"))
    )
    (net (code "61") (name "Net-(U10-MAG_SENSOR-CAP)") (class "Default")
      (node (ref "C8") (pin "1") (pinfunction "1_1") (pintype "passive"))
      (node (ref "U10-MAG_SENSOR") (pin "10") (pinfunction "CAP_10") (pintype "power_in"))
    )
    (net (code "62") (name "Net-(U11-EN)") (class "Default")
      (node (ref "C5") (pin "1") (pinfunction "1_1") (pintype "passive"))
      (node (ref "R8") (pin "2") (pinfunction "2_2") (pintype "passive"))
      (node (ref "U11") (pin "4") (pinfunction "VIN_4") (pintype "input"))
      (node (ref "U11") (pin "6") (pinfunction "EN_6") (pintype "input"))
    )
    (net (code "63") (name "Net-(U12-EN)") (class "Default")
      (node (ref "C12") (pin "1") (pinfunction "1_1") (pintype "passive"))
      (node (ref "R7") (pin "2") (pinfunction "2_2") (pintype "passive"))
      (node (ref "U12") (pin "1") (pinfunction "IN_1") (pintype "input"))
      (node (ref "U12") (pin "3") (pinfunction "EN_3") (pintype "input"))
    )
    (net (code "64") (name "unconnected-(DLHR-L30G-E1BD-C-NAV8-8-{slash}SS-Pad8-SS)") (class "Default")
      (node (ref "DLHR-L30G-E1BD-C-NAV8") (pin "8-SS") (pinfunction "8-/SS_8-SS") (pintype "bidirectional"))
    )
    (net (code "65") (name "unconnected-(DLHR-L30G-E1BD-C-NAV8-Pad5-EOC)") (class "Default")
      (node (ref "DLHR-L30G-E1BD-C-NAV8") (pin "5-EOC") (pinfunction "5-EOC_5-EOC") (pintype "bidirectional"))
    )
    (net (code "66") (name "unconnected-(DLHR-L30G-E1BD-C-NAV8-Pad6-MISO)") (class "Default")
      (node (ref "DLHR-L30G-E1BD-C-NAV8") (pin "6-MISO") (pinfunction "6-MISO_6-MISO") (pintype "bidirectional"))
    )
    (net (code "67") (name "unconnected-(DLHR-L30G-E1BD-C-NAV8-Pad7-NC)") (class "Default")
      (node (ref "DLHR-L30G-E1BD-C-NAV8") (pin "7-NC") (pinfunction "7-NC_7-NC") (pintype "bidirectional"))
    )
    (net (code "68") (name "unconnected-(IC2_ESP32S2WROOMM22S2-IO0-Pad3)") (class "Default")
      (node (ref "IC2_ESP32S2WROOMM22S2") (pin "3") (pinfunction "IO0_3") (pintype "bidirectional"))
    )
    (net (code "69") (name "unconnected-(IC2_ESP32S2WROOMM22S2-IO1-Pad4)") (class "Default")
      (node (ref "IC2_ESP32S2WROOMM22S2") (pin "4") (pinfunction "IO1_4") (pintype "bidirectional"))
    )
    (net (code "70") (name "unconnected-(IC2_ESP32S2WROOMM22S2-IO2-Pad5)") (class "Default")
      (node (ref "IC2_ESP32S2WROOMM22S2") (pin "5") (pinfunction "IO2_5") (pintype "bidirectional"))
    )
    (net (code "71") (name "unconnected-(IC2_ESP32S2WROOMM22S2-IO3-Pad6)") (class "Default")
      (node (ref "IC2_ESP32S2WROOMM22S2") (pin "6") (pinfunction "IO3_6") (pintype "bidirectional"))
    )
    (net (code "72") (name "unconnected-(IC2_ESP32S2WROOMM22S2-IO4-Pad7)") (class "Default")
      (node (ref "IC2_ESP32S2WROOMM22S2") (pin "7") (pinfunction "IO4_7") (pintype "bidirectional"))
    )
    (net (code "73") (name "unconnected-(IC2_ESP32S2WROOMM22S2-IO5-Pad8)") (class "Default")
      (node (ref "IC2_ESP32S2WROOMM22S2") (pin "8") (pinfunction "IO5_8") (pintype "bidirectional"))
    )
    (net (code "74") (name "unconnected-(IC2_ESP32S2WROOMM22S2-IO6-Pad9)") (class "Default")
      (node (ref "IC2_ESP32S2WROOMM22S2") (pin "9") (pinfunction "IO6_9") (pintype "bidirectional"))
    )
    (net (code "75") (name "unconnected-(IC2_ESP32S2WROOMM22S2-IO7-Pad10)") (class "Default")
      (node (ref "IC2_ESP32S2WROOMM22S2") (pin "10") (pinfunction "IO7_10") (pintype "bidirectional"))
    )
    (net (code "76") (name "unconnected-(IC2_ESP32S2WROOMM22S2-IO8-Pad11)") (class "Default")
      (node (ref "IC2_ESP32S2WROOMM22S2") (pin "11") (pinfunction "IO8_11") (pintype "bidirectional"))
    )
    (net (code "77") (name "unconnected-(IC2_ESP32S2WROOMM22S2-IO9-Pad12)") (class "Default")
      (node (ref "IC2_ESP32S2WROOMM22S2") (pin "12") (pinfunction "IO9_12") (pintype "bidirectional"))
    )
    (net (code "78") (name "unconnected-(IC2_ESP32S2WROOMM22S2-IO10-Pad13)") (class "Default")
      (node (ref "IC2_ESP32S2WROOMM22S2") (pin "13") (pinfunction "IO10_13") (pintype "bidirectional"))
    )
    (net (code "79") (name "unconnected-(IC2_ESP32S2WROOMM22S2-IO11-Pad14)") (class "Default")
      (node (ref "IC2_ESP32S2WROOMM22S2") (pin "14") (pinfunction "IO11_14") (pintype "bidirectional"))
    )
    (net (code "80") (name "unconnected-(IC2_ESP32S2WROOMM22S2-IO12-Pad15)") (class "Default")
      (node (ref "IC2_ESP32S2WROOMM22S2") (pin "15") (pinfunction "IO12_15") (pintype "bidirectional"))
    )
    (net (code "81") (name "unconnected-(IC2_ESP32S2WROOMM22S2-IO21-Pad24)") (class "Default")
      (node (ref "IC2_ESP32S2WROOMM22S2") (pin "24") (pinfunction "IO21_24") (pintype "bidirectional"))
    )
    (net (code "82") (name "unconnected-(IC2_ESP32S2WROOMM22S2-IO26-Pad25)") (class "Default")
      (node (ref "IC2_ESP32S2WROOMM22S2") (pin "25") (pinfunction "IO26_25") (pintype "bidirectional"))
    )
    (net (code "83") (name "unconnected-(IC2_ESP32S2WROOMM22S2-IO33-Pad27)") (class "Default")
      (node (ref "IC2_ESP32S2WROOMM22S2") (pin "27") (pinfunction "IO33_27") (pintype "bidirectional"))
    )
    (net (code "84") (name "unconnected-(IC2_ESP32S2WROOMM22S2-IO34-Pad28)") (class "Default")
      (node (ref "IC2_ESP32S2WROOMM22S2") (pin "28") (pinfunction "IO34_28") (pintype "bidirectional"))
    )
    (net (code "85") (name "unconnected-(IC2_ESP32S2WROOMM22S2-IO35-Pad29)") (class "Default")
      (node (ref "IC2_ESP32S2WROOMM22S2") (pin "29") (pinfunction "IO35_29") (pintype "bidirectional"))
    )
    (net (code "86") (name "unconnected-(IC2_ESP32S2WROOMM22S2-IO36-Pad30)") (class "Default")
      (node (ref "IC2_ESP32S2WROOMM22S2") (pin "30") (pinfunction "IO36_30") (pintype "bidirectional"))
    )
    (net (code "87") (name "unconnected-(IC2_ESP32S2WROOMM22S2-IO37-Pad31)") (class "Default")
      (node (ref "IC2_ESP32S2WROOMM22S2") (pin "31") (pinfunction "IO37_31") (pintype "bidirectional"))
    )
    (net (code "88") (name "unconnected-(IC2_ESP32S2WROOMM22S2-IO38-Pad32)") (class "Default")
      (node (ref "IC2_ESP32S2WROOMM22S2") (pin "32") (pinfunction "IO38_32") (pintype "bidirectional"))
    )
    (net (code "89") (name "unconnected-(IC2_ESP32S2WROOMM22S2-IO39-Pad33)") (class "Default")
      (node (ref "IC2_ESP32S2WROOMM22S2") (pin "33") (pinfunction "IO39_33") (pintype "bidirectional"))
    )
    (net (code "90") (name "unconnected-(IC2_ESP32S2WROOMM22S2-IO40-Pad34)") (class "Default")
      (node (ref "IC2_ESP32S2WROOMM22S2") (pin "34") (pinfunction "IO40_34") (pintype "bidirectional"))
    )
    (net (code "91") (name "unconnected-(IC2_ESP32S2WROOMM22S2-IO41-Pad35)") (class "Default")
      (node (ref "IC2_ESP32S2WROOMM22S2") (pin "35") (pinfunction "IO41_35") (pintype "bidirectional"))
    )
    (net (code "92") (name "unconnected-(IC2_ESP32S2WROOMM22S2-IO42-Pad36)") (class "Default")
      (node (ref "IC2_ESP32S2WROOMM22S2") (pin "36") (pinfunction "IO42_36") (pintype "bidirectional"))
    )
    (net (code "93") (name "unconnected-(J6_OAT-Pad4)") (class "Default")
      (node (ref "J6_OAT") (pin "4") (pinfunction "4_4") (pintype "bidirectional"))
    )
    (net (code "94") (name "unconnected-(U$4-Pad5-INT{slash}SS)") (class "Default")
      (node (ref "U$4") (pin "5-INT/SS") (pinfunction "5-INT/SS_5-INT/SS") (pintype "bidirectional"))
    )
    (net (code "95") (name "unconnected-(U$4-Pad6-NC)") (class "Default")
      (node (ref "U$4") (pin "6-NC") (pinfunction "6-NC_6-NC") (pintype "bidirectional"))
    )
    (net (code "96") (name "unconnected-(U$4-Pad7-NC)") (class "Default")
      (node (ref "U$4") (pin "7-NC") (pinfunction "7-NC_7-NC") (pintype "bidirectional"))
    )
    (net (code "97") (name "unconnected-(U$4-Pad8-NC)") (class "Default")
      (node (ref "U$4") (pin "8-NC") (pinfunction "8-NC_8-NC") (pintype "bidirectional"))
    )
    (net (code "98") (name "unconnected-(U1-INT_DRDY-Pad7)") (class "Default")
      (node (ref "U1") (pin "7") (pinfunction "INT_DRDY_7") (pintype "output"))
    )
    (net (code "99") (name "unconnected-(U2-INT_DRDY-Pad7)") (class "Default")
      (node (ref "U2") (pin "7") (pinfunction "INT_DRDY_7") (pintype "output"))
    )
    (net (code "100") (name "unconnected-(U3-IMU-INT1-Pad4)") (class "Default")
      (node (ref "U3-IMU") (pin "4") (pinfunction "INT1_4") (pintype "input"))
    )
    (net (code "101") (name "unconnected-(U3-IMU-INT2{slash}DEN{slash}MDRDY-Pad9)") (class "Default")
      (node (ref "U3-IMU") (pin "9") (pinfunction "INT2/DEN/MDRDY_9") (pintype "input"))
    )
    (net (code "102") (name "unconnected-(U3-IMU-OCS_AUX-Pad10)") (class "Default")
      (node (ref "U3-IMU") (pin "10") (pinfunction "OCS_AUX_10") (pintype "input"))
    )
    (net (code "103") (name "unconnected-(U3-IMU-SCX-Pad3)") (class "Default")
      (node (ref "U3-IMU") (pin "3") (pinfunction "SCX_3") (pintype "bidirectional"))
    )
    (net (code "104") (name "unconnected-(U3-IMU-SDO_AUX-Pad11)") (class "Default")
      (node (ref "U3-IMU") (pin "11") (pinfunction "SDO_AUX_11") (pintype "bidirectional"))
    )
    (net (code "105") (name "unconnected-(U3-IMU-SDO{slash}SA0-Pad1)") (class "Default")
      (node (ref "U3-IMU") (pin "1") (pinfunction "SDO/SA0_1") (pintype "bidirectional"))
    )
    (net (code "106") (name "unconnected-(U3-IMU-SDX-Pad2)") (class "Default")
      (node (ref "U3-IMU") (pin "2") (pinfunction "SDX_2") (pintype "bidirectional"))
    )
    (net (code "107") (name "unconnected-(U10-MAG_SENSOR-INT-Pad15)") (class "Default")
      (node (ref "U10-MAG_SENSOR") (pin "15") (pinfunction "INT_15") (pintype "output"))
    )
    (net (code "108") (name "unconnected-(U10-MAG_SENSOR-SDO-Pad5)") (class "Default")
      (node (ref "U10-MAG_SENSOR") (pin "5") (pinfunction "SDO_5") (pintype "bidirectional"))
    )
    (net (code "109") (name "unconnected-(U13-I2C-PCTLZ-Pad6)") (class "Default")
      (node (ref "U13-I2C") (pin "6") (pinfunction "PCTLZ_6") (pintype "output"))
    )
  )
)
